# watch.net
KiCad netlist of a schematic drawn in EAGLE
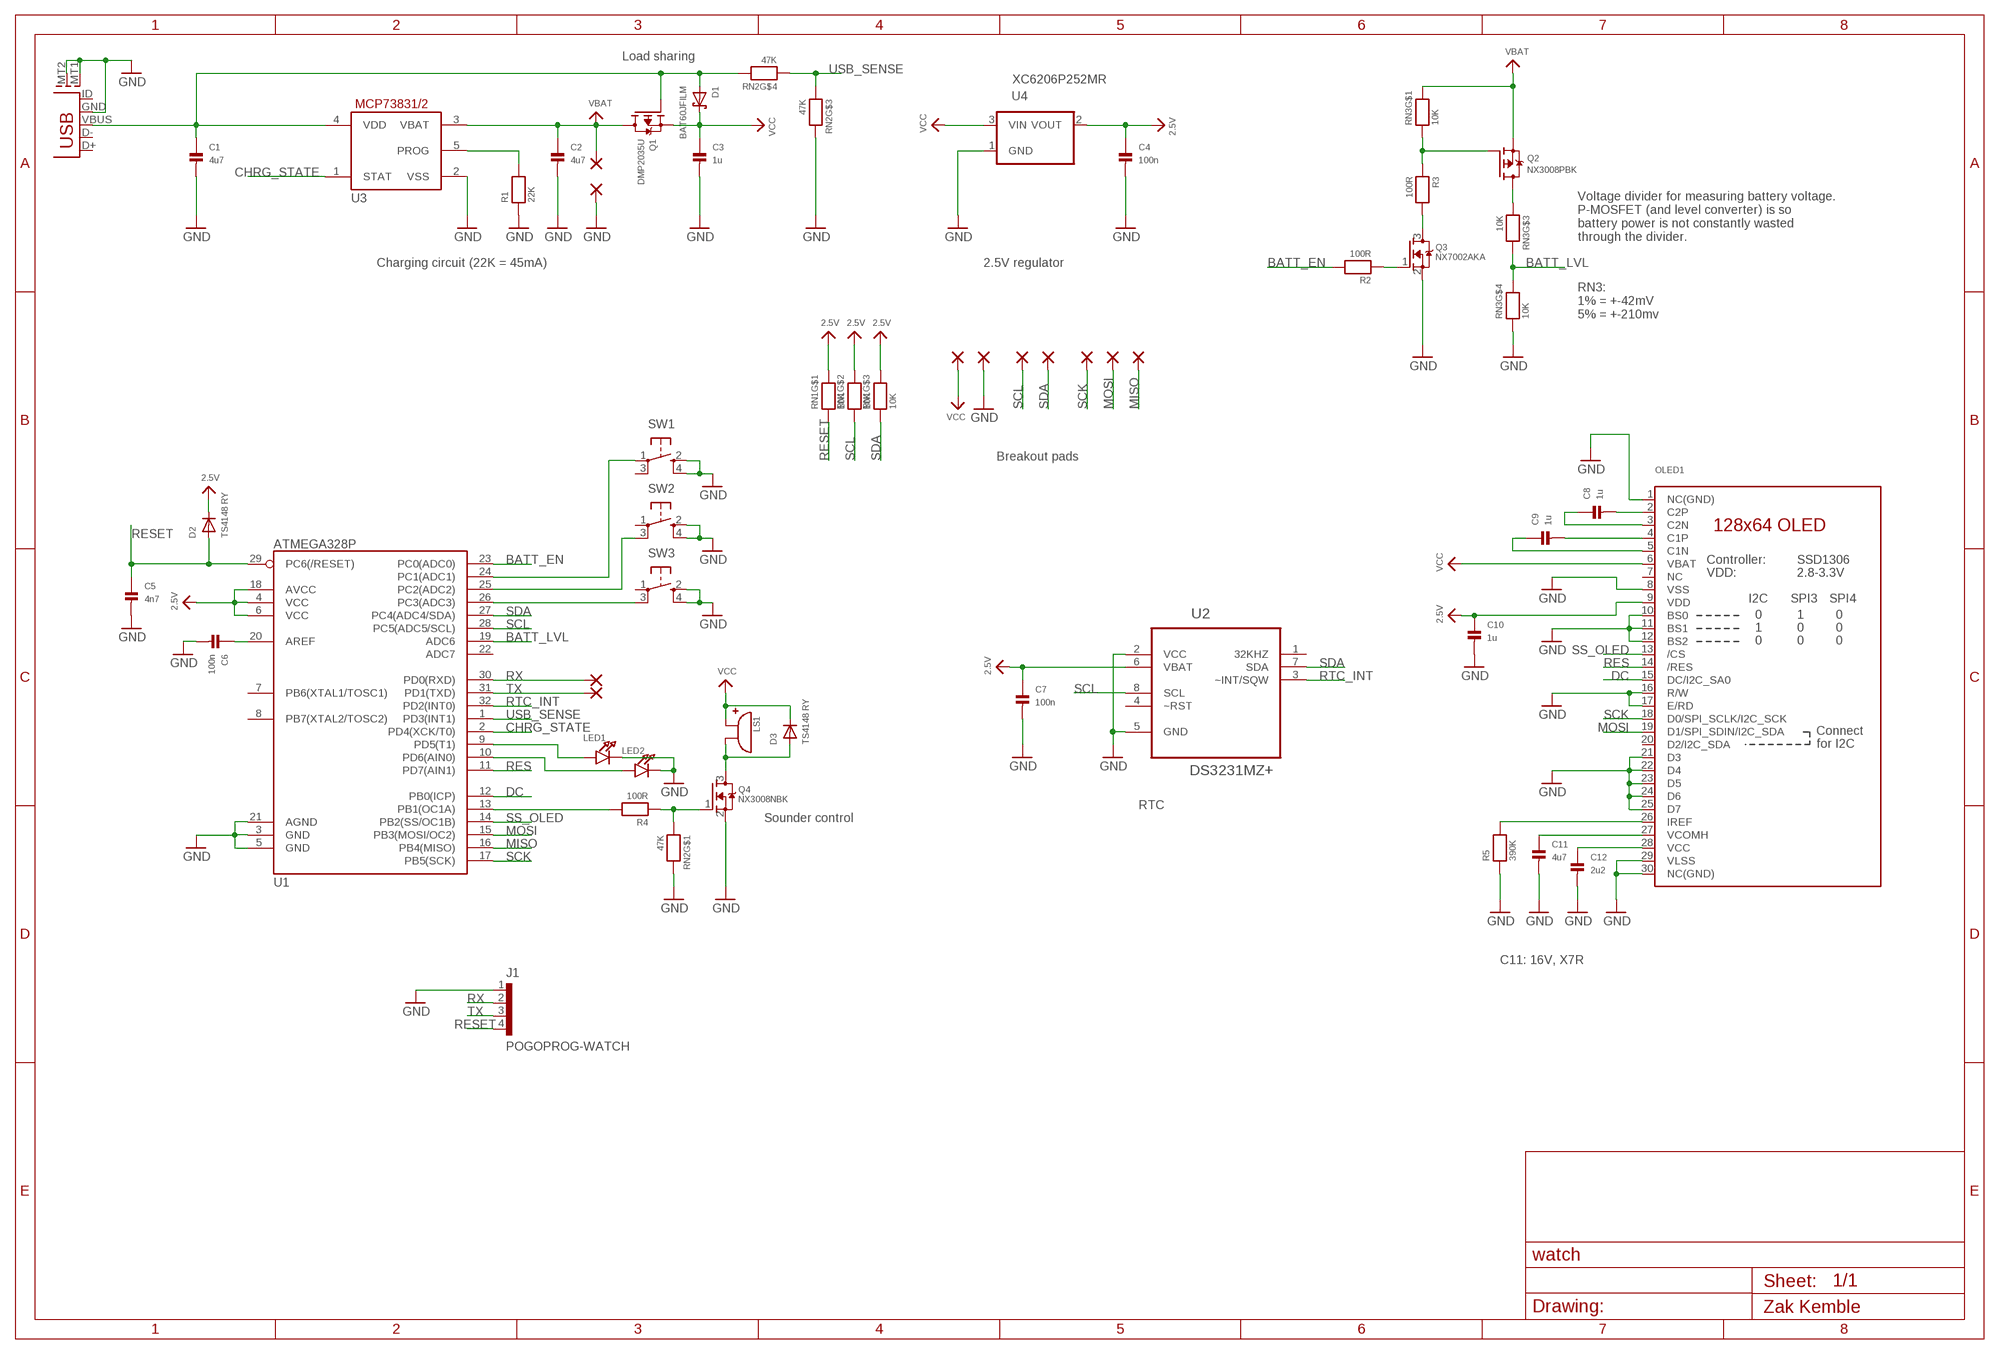
[diagram p0: schematic, sheet 1]

(export (version "E")
  (design (tool "Eeschema 10.0.6"))
  (components
    (comp (ref "C1")
      (value "4u7")
      (footprint "eagle-import:0805")
      (libsource (lib "eagle-import") (part "CAP_CERAMIC0805"))
    )
    (comp (ref "C2")
      (value "4u7")
      (footprint "eagle-import:0805")
      (libsource (lib "eagle-import") (part "CAP_CERAMIC0805"))
    )
    (comp (ref "C3")
      (value "1u")
      (footprint "eagle-import:0805")
      (libsource (lib "eagle-import") (part "CAP_CERAMIC0805"))
    )
    (comp (ref "C4")
      (value "100n")
      (footprint "eagle-import:0805")
      (libsource (lib "eagle-import") (part "CAP_CERAMIC0805"))
    )
    (comp (ref "C5")
      (value "4n7")
      (footprint "eagle-import:0805")
      (libsource (lib "eagle-import") (part "CAP_CERAMIC0805"))
    )
    (comp (ref "C6")
      (value "100n")
      (footprint "eagle-import:0805")
      (libsource (lib "eagle-import") (part "CAP_CERAMIC0805"))
    )
    (comp (ref "C7")
      (value "100n")
      (footprint "eagle-import:0805")
      (libsource (lib "eagle-import") (part "CAP_CERAMIC0805"))
    )
    (comp (ref "C8")
      (value "1u")
      (footprint "eagle-import:0805")
      (libsource (lib "eagle-import") (part "CAP_CERAMIC0805"))
    )
    (comp (ref "C9")
      (value "1u")
      (footprint "eagle-import:0805")
      (libsource (lib "eagle-import") (part "CAP_CERAMIC0805"))
    )
    (comp (ref "C10")
      (value "1u")
      (footprint "eagle-import:0805")
      (libsource (lib "eagle-import") (part "CAP_CERAMIC0805"))
    )
    (comp (ref "C11")
      (value "4u7")
      (footprint "eagle-import:0805")
      (libsource (lib "eagle-import") (part "CAP_CERAMIC0805"))
    )
    (comp (ref "C12")
      (value "2u2")
      (footprint "eagle-import:0805")
      (libsource (lib "eagle-import") (part "CAP_CERAMIC0805"))
    )
    (comp (ref "D1")
      (value "BAT60JFILM")
      (footprint "eagle-import:SOD-323")
      (libsource (lib "eagle-import") (part "DIODE-SCHOTTKYSOD-323"))
    )
    (comp (ref "D2")
      (value "TS4148 RY")
      (footprint "eagle-import:DIODE0805")
      (libsource (lib "eagle-import") (part "DIODE0805"))
    )
    (comp (ref "D3")
      (value "TS4148 RY")
      (footprint "eagle-import:DIODE0805")
      (libsource (lib "eagle-import") (part "DIODE0805"))
    )
    (comp (ref "J1")
      (value "POGOPROG-WATCH")
      (footprint "eagle-import:POGOPROG_WATCH")
      (libsource (lib "eagle-import") (part "POGOPROG-WATCH"))
    )
    (comp (ref "LED1")
      (value "LED0805")
      (footprint "eagle-import:CHIPLED_0805")
      (libsource (lib "eagle-import") (part "LED0805"))
    )
    (comp (ref "LED2")
      (value "LED0805")
      (footprint "eagle-import:CHIPLED_0805")
      (libsource (lib "eagle-import") (part "LED0805"))
    )
    (comp (ref "LS1")
      (value "ABMT-801-RC")
      (footprint "eagle-import:PIEZO")
      (libsource (lib "eagle-import") (part "ABMT-801-RC"))
    )
    (comp (ref "OLED1")
      (value "DISP_OLED_UG-2864HSWEG01_NOOUTLINEWATCH")
      (footprint "eagle-import:UG-2864HSWEG01_1.3_WRAPAROUND_WATCH")
      (libsource (lib "eagle-import") (part "DISP_OLED_UG-2864HSWEG01_NOOUTLINEWATCH"))
    )
    (comp (ref "PAD1")
      (value "SMD2")
      (footprint "eagle-import:SMD1,27-2,54")
      (libsource (lib "eagle-import") (part "SMD2"))
    )
    (comp (ref "PAD2")
      (value "SMD2")
      (footprint "eagle-import:SMD1,27-2,54")
      (libsource (lib "eagle-import") (part "SMD2"))
    )
    (comp (ref "PAD3")
      (value "SMD2")
      (footprint "eagle-import:SMD1,27-2,54")
      (libsource (lib "eagle-import") (part "SMD2"))
    )
    (comp (ref "PAD4")
      (value "SMD2")
      (footprint "eagle-import:SMD1,27-2,54")
      (libsource (lib "eagle-import") (part "SMD2"))
    )
    (comp (ref "PAD5")
      (value "SMD2")
      (footprint "eagle-import:SMD1,27-2,54")
      (libsource (lib "eagle-import") (part "SMD2"))
    )
    (comp (ref "PAD6")
      (value "SMD2")
      (footprint "eagle-import:SMD1,27-2,54")
      (libsource (lib "eagle-import") (part "SMD2"))
    )
    (comp (ref "PAD7")
      (value "SMD2")
      (footprint "eagle-import:SMD1,27-2,54")
      (libsource (lib "eagle-import") (part "SMD2"))
    )
    (comp (ref "PAD8")
      (value "SMD2")
      (footprint "eagle-import:SMD1,27-2,54")
      (libsource (lib "eagle-import") (part "SMD2"))
    )
    (comp (ref "PAD10")
      (value "SMD2")
      (footprint "eagle-import:SMD1,27-2,54")
      (libsource (lib "eagle-import") (part "SMD2"))
    )
    (comp (ref "PAD11")
      (value "SMD2")
      (footprint "eagle-import:SMD1,27-2,54")
      (libsource (lib "eagle-import") (part "SMD2"))
    )
    (comp (ref "PAD12")
      (value "SMD2")
      (footprint "eagle-import:SMD1,27-2,54")
      (libsource (lib "eagle-import") (part "SMD2"))
    )
    (comp (ref "Q1")
      (value "DMP2035U")
      (footprint "eagle-import:SOT23-WIDE")
      (libsource (lib "eagle-import") (part "MOSFET-PWIDE"))
    )
    (comp (ref "Q2")
      (value "NX3008PBK")
      (footprint "eagle-import:SOT23-WIDE")
      (libsource (lib "eagle-import") (part "MOSFET-PWIDE"))
    )
    (comp (ref "Q3")
      (value "NX7002AKA")
      (footprint "eagle-import:SOT23-WIDE")
      (libsource (lib "eagle-import") (part "MOSFET-NWIDE"))
    )
    (comp (ref "Q4")
      (value "NX3008NBK")
      (footprint "eagle-import:SOT23-WIDE")
      (libsource (lib "eagle-import") (part "MOSFET-NWIDE"))
    )
    (comp (ref "R1")
      (value "22K")
      (footprint "eagle-import:0805")
      (libsource (lib "eagle-import") (part "RESISTOR0805"))
    )
    (comp (ref "R2")
      (value "100R")
      (footprint "eagle-import:0805")
      (libsource (lib "eagle-import") (part "RESISTOR0805"))
    )
    (comp (ref "R3")
      (value "100R")
      (footprint "eagle-import:0805")
      (libsource (lib "eagle-import") (part "RESISTOR0805"))
    )
    (comp (ref "R4")
      (value "100R")
      (footprint "eagle-import:0805")
      (libsource (lib "eagle-import") (part "RESISTOR0805"))
    )
    (comp (ref "R5")
      (value "390K")
      (footprint "eagle-import:0805")
      (libsource (lib "eagle-import") (part "RESISTOR0805"))
    )
    (comp (ref "RN1")
      (value "10K")
      (footprint "eagle-import:RESPACK_4X0603")
      (libsource (lib "eagle-import") (part "RESISTOR_4PACK"))
    )
    (comp (ref "RN2")
      (value "47K")
      (footprint "eagle-import:RESPACK_4X0603")
      (libsource (lib "eagle-import") (part "RESISTOR_4PACK"))
    )
    (comp (ref "RN3")
      (value "10K")
      (footprint "eagle-import:RESPACK_4X0603")
      (libsource (lib "eagle-import") (part "RESISTOR_4PACK"))
    )
    (comp (ref "SW1")
      (value "SPST_TACTRA")
      (footprint "eagle-import:TACT_SMD2")
      (libsource (lib "eagle-import") (part "SPST_TACTRA"))
    )
    (comp (ref "SW2")
      (value "SPST_TACTRA")
      (footprint "eagle-import:TACT_SMD2")
      (libsource (lib "eagle-import") (part "SPST_TACTRA"))
    )
    (comp (ref "SW3")
      (value "SPST_TACTRA")
      (footprint "eagle-import:TACT_SMD2")
      (libsource (lib "eagle-import") (part "SPST_TACTRA"))
    )
    (comp (ref "U1")
      (value "ATMEGA328P")
      (footprint "eagle-import:TQFP32-08")
      (libsource (lib "eagle-import") (part "ATMEGA328_SMT"))
    )
    (comp (ref "U2")
      (value "DS3231MZ+")
      (footprint "eagle-import:SOIC8_150MIL")
      (libsource (lib "eagle-import") (part "DS3231MZ+"))
    )
    (comp (ref "U3")
      (value "MCP73832T-2ACI/OT")
      (footprint "eagle-import:SOT23-5L")
      (libsource (lib "eagle-import") (part "MCP73831/OT"))
    )
    (comp (ref "U4")
      (value "XC6206P252MR")
      (footprint "eagle-import:SOT-23")
      (libsource (lib "eagle-import") (part "MCP1700T-2502E/TTWIDE_PAD"))
    )
    (comp (ref "USB1")
      (value "USB-MICROBLARGEPAD")
      (footprint "eagle-import:USB-MICROB_LARGEPAD")
      (libsource (lib "eagle-import") (part "USB-MICROBLARGEPAD"))
    )
  )
  (nets
    (net (code "1") (name "/BATT_EN") (class "Default")
      (node (ref "R2") (pin "2") (pinfunction "2_2") (pintype "passive"))
      (node (ref "U1") (pin "23") (pinfunction "PC0(ADC0)_23") (pintype "bidirectional"))
    )
    (net (code "2") (name "/BATT_LVL") (class "Default")
      (node (ref "RN3") (pin "5") (pinfunction "2_5") (pintype "passive"))
      (node (ref "RN3") (pin "6") (pinfunction "2_6") (pintype "passive"))
      (node (ref "U1") (pin "19") (pinfunction "ADC6_19") (pintype "bidirectional"))
    )
    (net (code "3") (name "/CHRG_STATE") (class "Default")
      (node (ref "U1") (pin "2") (pinfunction "PD4(XCK/T0)_2") (pintype "bidirectional"))
      (node (ref "U3") (pin "1") (pinfunction "STAT_1") (pintype "output"))
    )
    (net (code "4") (name "/DC") (class "Default")
      (node (ref "OLED1") (pin "15") (pinfunction "DC/I2C_SA0_15") (pintype "input"))
      (node (ref "U1") (pin "12") (pinfunction "PB0(ICP)_12") (pintype "bidirectional"))
    )
    (net (code "5") (name "/MISO") (class "Default")
      (node (ref "PAD12") (pin "1") (pinfunction "P_1") (pintype "passive"))
      (node (ref "U1") (pin "16") (pinfunction "PB4(MISO)_16") (pintype "bidirectional"))
    )
    (net (code "6") (name "/MOSI") (class "Default")
      (node (ref "OLED1") (pin "19") (pinfunction "D1/SPI_SDIN/I2C_SDA_19") (pintype "bidirectional"))
      (node (ref "PAD11") (pin "1") (pinfunction "P_1") (pintype "passive"))
      (node (ref "U1") (pin "15") (pinfunction "PB3(MOSI/OC2)_15") (pintype "bidirectional"))
    )
    (net (code "7") (name "/RES") (class "Default")
      (node (ref "OLED1") (pin "14") (pinfunction "/RES_14") (pintype "input"))
      (node (ref "U1") (pin "11") (pinfunction "PD7(AIN1)_11") (pintype "bidirectional"))
    )
    (net (code "8") (name "/RESET") (class "Default")
      (node (ref "C5") (pin "1") (pinfunction "P$1_1") (pintype "passive"))
      (node (ref "D2") (pin "1") (pinfunction "A_1") (pintype "passive"))
      (node (ref "J1") (pin "4") (pinfunction "4_4") (pintype "bidirectional"))
      (node (ref "RN1") (pin "1") (pinfunction "1_1") (pintype "passive"))
      (node (ref "U1") (pin "29") (pinfunction "PC6(/RESET)_29") (pintype "bidirectional"))
    )
    (net (code "9") (name "/RTC_INT") (class "Default")
      (node (ref "U1") (pin "32") (pinfunction "PD2(INT0)_32") (pintype "bidirectional"))
      (node (ref "U2") (pin "3") (pinfunction "~{INT/SQW}_3") (pintype "output"))
    )
    (net (code "10") (name "/RX") (class "Default")
      (node (ref "J1") (pin "2") (pinfunction "2_2") (pintype "bidirectional"))
      (node (ref "PAD3") (pin "1") (pinfunction "P_1") (pintype "passive"))
      (node (ref "U1") (pin "30") (pinfunction "PD0(RXD)_30") (pintype "bidirectional"))
    )
    (net (code "11") (name "/SCK") (class "Default")
      (node (ref "OLED1") (pin "18") (pinfunction "D0/SPI_SCLK/I2C_SCK_18") (pintype "bidirectional"))
      (node (ref "PAD10") (pin "1") (pinfunction "P_1") (pintype "passive"))
      (node (ref "U1") (pin "17") (pinfunction "PB5(SCK)_17") (pintype "bidirectional"))
    )
    (net (code "12") (name "/SCL") (class "Default")
      (node (ref "PAD8") (pin "1") (pinfunction "P_1") (pintype "passive"))
      (node (ref "RN1") (pin "2") (pinfunction "1_2") (pintype "passive"))
      (node (ref "U1") (pin "28") (pinfunction "PC5(ADC5/SCL)_28") (pintype "bidirectional"))
      (node (ref "U2") (pin "8") (pinfunction "SCL_8") (pintype "input"))
    )
    (net (code "13") (name "/SDA") (class "Default")
      (node (ref "PAD7") (pin "1") (pinfunction "P_1") (pintype "passive"))
      (node (ref "RN1") (pin "3") (pinfunction "1_3") (pintype "passive"))
      (node (ref "U1") (pin "27") (pinfunction "PC4(ADC4/SDA)_27") (pintype "bidirectional"))
      (node (ref "U2") (pin "7") (pinfunction "SDA_7") (pintype "bidirectional"))
    )
    (net (code "14") (name "/SS_OLED") (class "Default")
      (node (ref "OLED1") (pin "13") (pinfunction "/CS_13") (pintype "input"))
      (node (ref "U1") (pin "14") (pinfunction "PB2(SS/OC1B)_14") (pintype "bidirectional"))
    )
    (net (code "15") (name "/TX") (class "Default")
      (node (ref "J1") (pin "3") (pinfunction "3_3") (pintype "bidirectional"))
      (node (ref "PAD4") (pin "1") (pinfunction "P_1") (pintype "passive"))
      (node (ref "U1") (pin "31") (pinfunction "PD1(TXD)_31") (pintype "bidirectional"))
    )
    (net (code "16") (name "/USB_SENSE") (class "Default")
      (node (ref "RN2") (pin "3") (pinfunction "1_3") (pintype "passive"))
      (node (ref "RN2") (pin "4") (pinfunction "1_4") (pintype "passive"))
      (node (ref "U1") (pin "1") (pinfunction "PD3(INT1)_1") (pintype "bidirectional"))
    )
    (net (code "17") (name "2.5V") (class "Default")
      (node (ref "C10") (pin "1") (pinfunction "P$1_1") (pintype "passive"))
      (node (ref "C4") (pin "1") (pinfunction "P$1_1") (pintype "passive"))
      (node (ref "C7") (pin "1") (pinfunction "P$1_1") (pintype "passive"))
      (node (ref "D2") (pin "2") (pinfunction "C_2") (pintype "passive"))
      (node (ref "OLED1") (pin "9") (pinfunction "VDD_9") (pintype "power_in"))
      (node (ref "RN1") (pin "6") (pinfunction "2_6") (pintype "passive"))
      (node (ref "RN1") (pin "7") (pinfunction "2_7") (pintype "passive"))
      (node (ref "RN1") (pin "8") (pinfunction "2_8") (pintype "passive"))
      (node (ref "U1") (pin "18") (pinfunction "AVCC_18") (pintype "bidirectional"))
      (node (ref "U1") (pin "4") (pinfunction "VCC_4") (pintype "bidirectional"))
      (node (ref "U1") (pin "6") (pinfunction "VCC_6") (pintype "bidirectional"))
      (node (ref "U2") (pin "6") (pinfunction "VBAT_6") (pintype "power_in"))
      (node (ref "U4") (pin "2") (pinfunction "VOUT_2") (pintype "output"))
    )
    (net (code "18") (name "GND") (class "Default")
      (node (ref "C1") (pin "2") (pinfunction "P$2_2") (pintype "passive"))
      (node (ref "C10") (pin "2") (pinfunction "P$2_2") (pintype "passive"))
      (node (ref "C11") (pin "2") (pinfunction "P$2_2") (pintype "passive"))
      (node (ref "C12") (pin "2") (pinfunction "P$2_2") (pintype "passive"))
      (node (ref "C2") (pin "2") (pinfunction "P$2_2") (pintype "passive"))
      (node (ref "C3") (pin "2") (pinfunction "P$2_2") (pintype "passive"))
      (node (ref "C4") (pin "2") (pinfunction "P$2_2") (pintype "passive"))
      (node (ref "C5") (pin "2") (pinfunction "P$2_2") (pintype "passive"))
      (node (ref "C6") (pin "2") (pinfunction "P$2_2") (pintype "passive"))
      (node (ref "C7") (pin "2") (pinfunction "P$2_2") (pintype "passive"))
      (node (ref "J1") (pin "1") (pinfunction "1_1") (pintype "bidirectional"))
      (node (ref "LED1") (pin "C") (pinfunction "C_C") (pintype "passive"))
      (node (ref "LED2") (pin "C") (pinfunction "C_C") (pintype "passive"))
      (node (ref "OLED1") (pin "1") (pinfunction "NC(GND)_1") (pintype "input"))
      (node (ref "OLED1") (pin "10") (pinfunction "BS0_10") (pintype "input"))
      (node (ref "OLED1") (pin "11") (pinfunction "BS1_11") (pintype "input"))
      (node (ref "OLED1") (pin "12") (pinfunction "BS2_12") (pintype "input"))
      (node (ref "OLED1") (pin "16") (pinfunction "R/W_16") (pintype "input"))
      (node (ref "OLED1") (pin "17") (pinfunction "E/RD_17") (pintype "input"))
      (node (ref "OLED1") (pin "21") (pinfunction "D3_21") (pintype "bidirectional"))
      (node (ref "OLED1") (pin "22") (pinfunction "D4_22") (pintype "bidirectional"))
      (node (ref "OLED1") (pin "23") (pinfunction "D5_23") (pintype "bidirectional"))
      (node (ref "OLED1") (pin "24") (pinfunction "D6_24") (pintype "bidirectional"))
      (node (ref "OLED1") (pin "25") (pinfunction "D7_25") (pintype "bidirectional"))
      (node (ref "OLED1") (pin "29") (pinfunction "VLSS_29") (pintype "power_in"))
      (node (ref "OLED1") (pin "30") (pinfunction "NC(GND)_30") (pintype "input"))
      (node (ref "OLED1") (pin "8") (pinfunction "VSS_8") (pintype "power_in"))
      (node (ref "PAD2") (pin "1") (pinfunction "P_1") (pintype "passive"))
      (node (ref "PAD5") (pin "1") (pinfunction "P_1") (pintype "passive"))
      (node (ref "Q3") (pin "2") (pinfunction "S_2") (pintype "bidirectional"))
      (node (ref "Q4") (pin "2") (pinfunction "S_2") (pintype "bidirectional"))
      (node (ref "R1") (pin "1") (pinfunction "1_1") (pintype "passive"))
      (node (ref "R5") (pin "1") (pinfunction "1_1") (pintype "passive"))
      (node (ref "RN2") (pin "6") (pinfunction "2_6") (pintype "passive"))
      (node (ref "RN2") (pin "8") (pinfunction "2_8") (pintype "passive"))
      (node (ref "RN3") (pin "4") (pinfunction "1_4") (pintype "passive"))
      (node (ref "SW1") (pin "2") (pinfunction "S_2") (pintype "passive"))
      (node (ref "SW1") (pin "4") (pinfunction "S1_4") (pintype "passive"))
      (node (ref "SW2") (pin "2") (pinfunction "S_2") (pintype "passive"))
      (node (ref "SW2") (pin "4") (pinfunction "S1_4") (pintype "passive"))
      (node (ref "SW3") (pin "2") (pinfunction "S_2") (pintype "passive"))
      (node (ref "SW3") (pin "4") (pinfunction "S1_4") (pintype "passive"))
      (node (ref "U1") (pin "21") (pinfunction "AGND_21") (pintype "bidirectional"))
      (node (ref "U1") (pin "3") (pinfunction "GND_3") (pintype "bidirectional"))
      (node (ref "U1") (pin "5") (pinfunction "GND_5") (pintype "bidirectional"))
      (node (ref "U2") (pin "2") (pinfunction "VCC_2") (pintype "power_in"))
      (node (ref "U2") (pin "5") (pinfunction "GND_5") (pintype "passive"))
      (node (ref "U3") (pin "2") (pinfunction "VSS_2") (pintype "power_in"))
      (node (ref "U4") (pin "1") (pinfunction "GND_1") (pintype "passive"))
      (node (ref "USB1") (pin "GND") (pinfunction "GND_GND") (pintype "bidirectional"))
      (node (ref "USB1") (pin "MT1") (pinfunction "SHEILD1_MT1") (pintype "bidirectional"))
      (node (ref "USB1") (pin "MT2") (pinfunction "SHEILD2_MT2") (pintype "bidirectional"))
    )
    (net (code "19") (name "Net-(C1-P$1)") (class "Default")
      (node (ref "C1") (pin "1") (pinfunction "P$1_1") (pintype "passive"))
      (node (ref "D1") (pin "A") (pinfunction "A_A") (pintype "passive"))
      (node (ref "Q1") (pin "1") (pinfunction "G_1") (pintype "passive"))
      (node (ref "RN2") (pin "5") (pinfunction "2_5") (pintype "passive"))
      (node (ref "U3") (pin "4") (pinfunction "VDD_4") (pintype "power_in"))
      (node (ref "USB1") (pin "VBUS") (pinfunction "VBUS_VBUS") (pintype "bidirectional"))
    )
    (net (code "20") (name "Net-(C6-P$1)") (class "Default")
      (node (ref "C6") (pin "1") (pinfunction "P$1_1") (pintype "passive"))
      (node (ref "U1") (pin "20") (pinfunction "AREF_20") (pintype "bidirectional"))
    )
    (net (code "21") (name "Net-(C8-P$1)") (class "Default")
      (node (ref "C8") (pin "1") (pinfunction "P$1_1") (pintype "passive"))
      (node (ref "OLED1") (pin "3") (pinfunction "C2N_3") (pintype "input"))
    )
    (net (code "22") (name "Net-(C8-P$2)") (class "Default")
      (node (ref "C8") (pin "2") (pinfunction "P$2_2") (pintype "passive"))
      (node (ref "OLED1") (pin "2") (pinfunction "C2P_2") (pintype "input"))
    )
    (net (code "23") (name "Net-(C9-P$1)") (class "Default")
      (node (ref "C9") (pin "1") (pinfunction "P$1_1") (pintype "passive"))
      (node (ref "OLED1") (pin "5") (pinfunction "C1N_5") (pintype "input"))
    )
    (net (code "24") (name "Net-(C9-P$2)") (class "Default")
      (node (ref "C9") (pin "2") (pinfunction "P$2_2") (pintype "passive"))
      (node (ref "OLED1") (pin "4") (pinfunction "C1P_4") (pintype "input"))
    )
    (net (code "25") (name "Net-(C11-P$1)") (class "Default")
      (node (ref "C11") (pin "1") (pinfunction "P$1_1") (pintype "passive"))
      (node (ref "OLED1") (pin "27") (pinfunction "VCOMH_27") (pintype "output"))
    )
    (net (code "26") (name "Net-(C12-P$1)") (class "Default")
      (node (ref "C12") (pin "1") (pinfunction "P$1_1") (pintype "passive"))
      (node (ref "OLED1") (pin "28") (pinfunction "VCC_28") (pintype "power_in"))
    )
    (net (code "27") (name "Net-(D3-A)") (class "Default")
      (node (ref "D3") (pin "1") (pinfunction "A_1") (pintype "passive"))
      (node (ref "LS1") (pin "2") (pinfunction "GND_2") (pintype "passive"))
      (node (ref "Q4") (pin "3") (pinfunction "D_3") (pintype "bidirectional"))
    )
    (net (code "28") (name "Net-(OLED1-IREF)") (class "Default")
      (node (ref "OLED1") (pin "26") (pinfunction "IREF_26") (pintype "input"))
      (node (ref "R5") (pin "2") (pinfunction "2_2") (pintype "passive"))
    )
    (net (code "29") (name "Net-(Q2-D)") (class "Default")
      (node (ref "Q2") (pin "3") (pinfunction "D_3") (pintype "passive"))
      (node (ref "RN3") (pin "3") (pinfunction "1_3") (pintype "passive"))
    )
    (net (code "30") (name "Net-(Q2-G)") (class "Default")
      (node (ref "Q2") (pin "1") (pinfunction "G_1") (pintype "passive"))
      (node (ref "R3") (pin "1") (pinfunction "1_1") (pintype "passive"))
      (node (ref "RN3") (pin "1") (pinfunction "1_1") (pintype "passive"))
    )
    (net (code "31") (name "Net-(Q3-D)") (class "Default")
      (node (ref "Q3") (pin "3") (pinfunction "D_3") (pintype "bidirectional"))
      (node (ref "R3") (pin "2") (pinfunction "2_2") (pintype "passive"))
    )
    (net (code "32") (name "Net-(Q3-G)") (class "Default")
      (node (ref "Q3") (pin "1") (pinfunction "G_1") (pintype "bidirectional"))
      (node (ref "R2") (pin "1") (pinfunction "1_1") (pintype "passive"))
    )
    (net (code "33") (name "Net-(Q4-G)") (class "Default")
      (node (ref "Q4") (pin "1") (pinfunction "G_1") (pintype "bidirectional"))
      (node (ref "R4") (pin "1") (pinfunction "1_1") (pintype "passive"))
      (node (ref "RN2") (pin "1") (pinfunction "1_1") (pintype "passive"))
    )
    (net (code "34") (name "Net-(SW1-P)") (class "Default")
      (node (ref "SW1") (pin "1") (pinfunction "P_1") (pintype "passive"))
      (node (ref "U1") (pin "24") (pinfunction "PC1(ADC1)_24") (pintype "bidirectional"))
    )
    (net (code "35") (name "Net-(SW2-P1)") (class "Default")
      (node (ref "SW2") (pin "3") (pinfunction "P1_3") (pintype "passive"))
      (node (ref "U1") (pin "25") (pinfunction "PC2(ADC2)_25") (pintype "bidirectional"))
    )
    (net (code "36") (name "Net-(SW3-P1)") (class "Default")
      (node (ref "SW3") (pin "3") (pinfunction "P1_3") (pintype "passive"))
      (node (ref "U1") (pin "26") (pinfunction "PC3(ADC3)_26") (pintype "bidirectional"))
    )
    (net (code "37") (name "Net-(U1-PB1(OC1A))") (class "Default")
      (node (ref "R4") (pin "2") (pinfunction "2_2") (pintype "passive"))
      (node (ref "U1") (pin "13") (pinfunction "PB1(OC1A)_13") (pintype "bidirectional"))
    )
    (net (code "38") (name "Net-(U1-PD5(T1))") (class "Default")
      (node (ref "LED1") (pin "A") (pinfunction "A_A") (pintype "passive"))
      (node (ref "U1") (pin "9") (pinfunction "PD5(T1)_9") (pintype "bidirectional"))
    )
    (net (code "39") (name "Net-(U1-PD6(AIN0))") (class "Default")
      (node (ref "LED2") (pin "A") (pinfunction "A_A") (pintype "passive"))
      (node (ref "U1") (pin "10") (pinfunction "PD6(AIN0)_10") (pintype "bidirectional"))
    )
    (net (code "40") (name "Net-(U3-PROG)") (class "Default")
      (node (ref "R1") (pin "2") (pinfunction "2_2") (pintype "passive"))
      (node (ref "U3") (pin "5") (pinfunction "PROG_5") (pintype "input"))
    )
    (net (code "41") (name "VBAT") (class "Default")
      (node (ref "C2") (pin "1") (pinfunction "P$1_1") (pintype "passive"))
      (node (ref "PAD1") (pin "1") (pinfunction "P_1") (pintype "passive"))
      (node (ref "Q1") (pin "3") (pinfunction "D_3") (pintype "passive"))
      (node (ref "Q2") (pin "2") (pinfunction "S_2") (pintype "passive"))
      (node (ref "RN3") (pin "8") (pinfunction "2_8") (pintype "passive"))
      (node (ref "U3") (pin "3") (pinfunction "VBAT_3") (pintype "bidirectional"))
    )
    (net (code "42") (name "VCC") (class "Default")
      (node (ref "C3") (pin "1") (pinfunction "P$1_1") (pintype "passive"))
      (node (ref "D1") (pin "C") (pinfunction "C_C") (pintype "passive"))
      (node (ref "D3") (pin "2") (pinfunction "C_2") (pintype "passive"))
      (node (ref "LS1") (pin "1") (pinfunction "VCC_1") (pintype "passive"))
      (node (ref "OLED1") (pin "6") (pinfunction "VBAT_6") (pintype "input"))
      (node (ref "PAD6") (pin "1") (pinfunction "P_1") (pintype "passive"))
      (node (ref "Q1") (pin "2") (pinfunction "S_2") (pintype "passive"))
      (node (ref "U4") (pin "3") (pinfunction "VIN_3") (pintype "power_in"))
    )
    (net (code "43") (name "unconnected-(OLED1-D2{slash}I2C_SDA-Pad20)") (class "Default")
      (node (ref "OLED1") (pin "20") (pinfunction "D2/I2C_SDA_20") (pintype "bidirectional"))
    )
    (net (code "44") (name "unconnected-(OLED1-NC-Pad7)") (class "Default")
      (node (ref "OLED1") (pin "7") (pinfunction "NC_7") (pintype "no_connect"))
    )
    (net (code "45") (name "unconnected-(SW1-P1-Pad3)") (class "Default")
      (node (ref "SW1") (pin "3") (pinfunction "P1_3") (pintype "passive"))
    )
    (net (code "46") (name "unconnected-(SW2-P-Pad1)") (class "Default")
      (node (ref "SW2") (pin "1") (pinfunction "P_1") (pintype "passive"))
    )
    (net (code "47") (name "unconnected-(SW3-P-Pad1)") (class "Default")
      (node (ref "SW3") (pin "1") (pinfunction "P_1") (pintype "passive"))
    )
    (net (code "48") (name "unconnected-(U1-ADC7-Pad22)") (class "Default")
      (node (ref "U1") (pin "22") (pinfunction "ADC7_22") (pintype "bidirectional"))
    )
    (net (code "49") (name "unconnected-(U1-PB6(XTAL1{slash}TOSC1)-Pad7)") (class "Default")
      (node (ref "U1") (pin "7") (pinfunction "PB6(XTAL1/TOSC1)_7") (pintype "bidirectional"))
    )
    (net (code "50") (name "unconnected-(U1-PB7(XTAL2{slash}TOSC2)-Pad8)") (class "Default")
      (node (ref "U1") (pin "8") (pinfunction "PB7(XTAL2/TOSC2)_8") (pintype "bidirectional"))
    )
    (net (code "51") (name "unconnected-(U2-32KHZ-Pad1)") (class "Default")
      (node (ref "U2") (pin "1") (pinfunction "32KHZ_1") (pintype "output"))
    )
    (net (code "52") (name "unconnected-(U2-~{RST}-Pad4)") (class "Default")
      (node (ref "U2") (pin "4") (pinfunction "~{RST}_4") (pintype "bidirectional"))
    )
    (net (code "53") (name "unconnected-(USB1-PadD+)") (class "Default")
      (node (ref "USB1") (pin "D+") (pinfunction "D+_D+") (pintype "bidirectional"))
    )
    (net (code "54") (name "unconnected-(USB1-PadD-)") (class "Default")
      (node (ref "USB1") (pin "D-") (pinfunction "D-_D-") (pintype "bidirectional"))
    )
    (net (code "55") (name "unconnected-(USB1-PadID)") (class "Default")
      (node (ref "USB1") (pin "ID") (pinfunction "ID_ID") (pintype "bidirectional"))
    )
  )
)
